# Schematic_Transmitter.net
KiCad netlist of a schematic drawn in EasyEDA
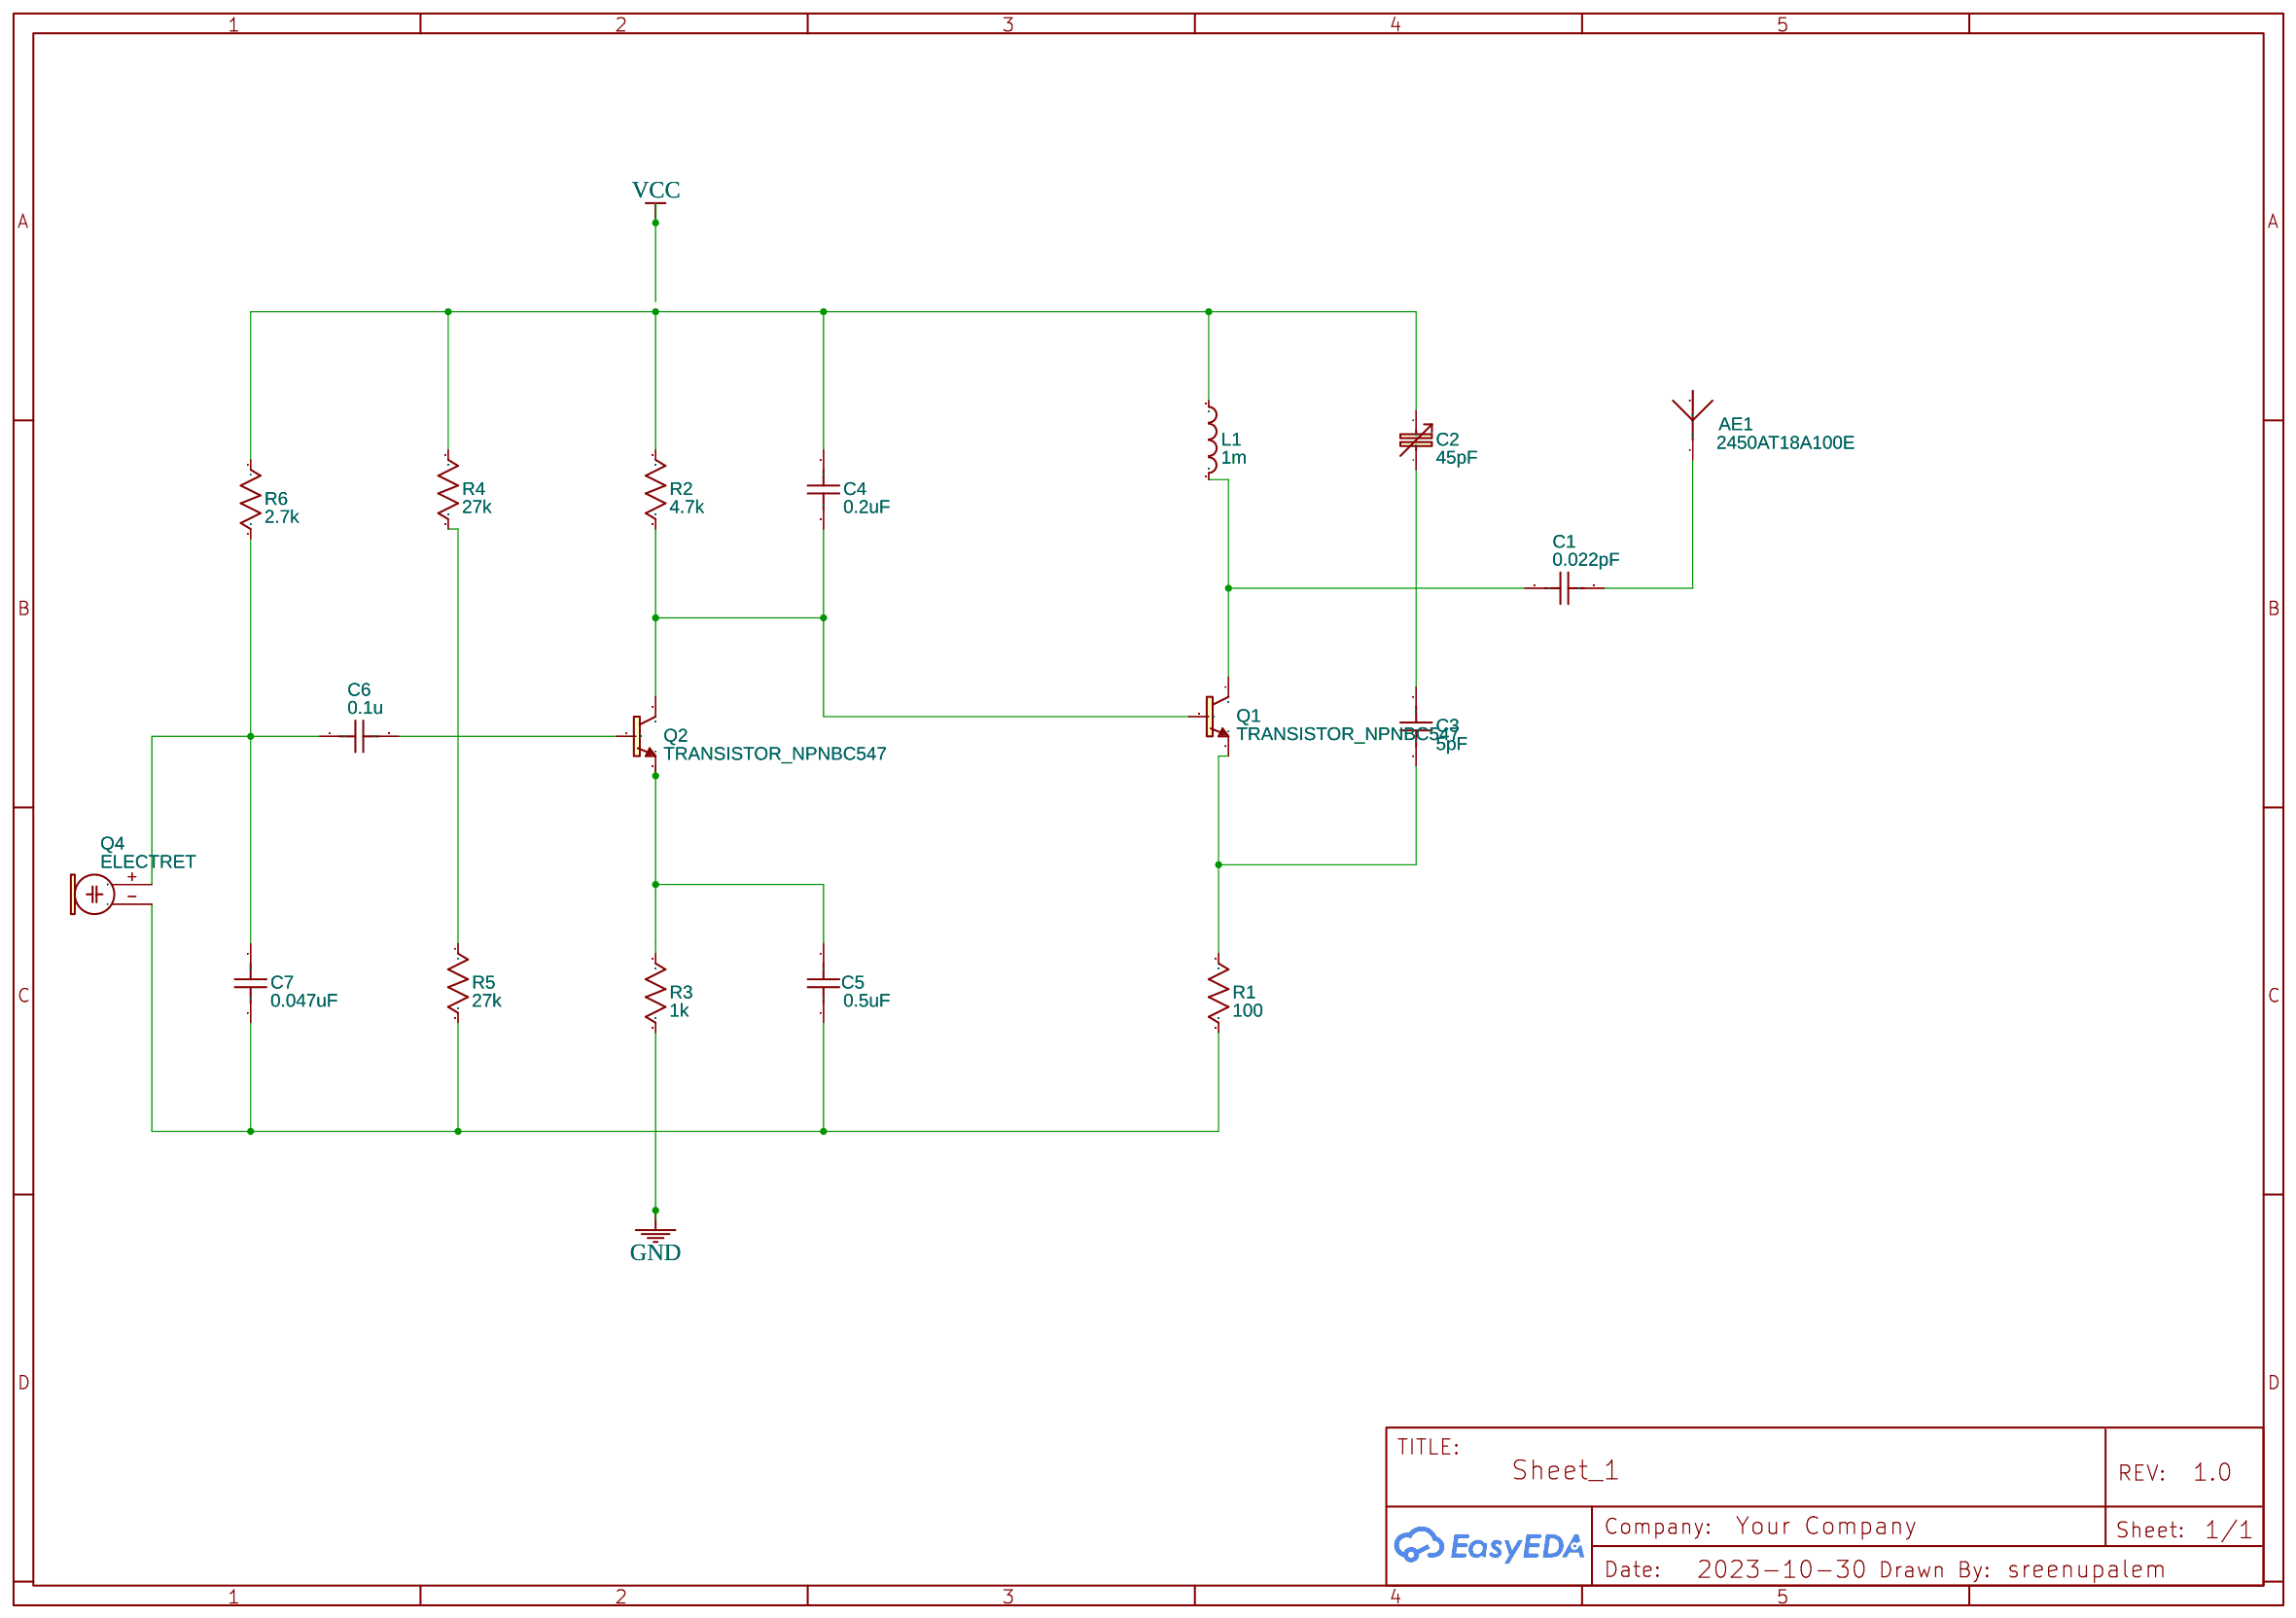
[diagram p0: schematic sheet]

(export (version "E")
  (design (tool "Eeschema 10.0.6"))
  (components
    (comp (ref "AE1")
      (value "2450AT18A100E")
      (fields (field (name "Manufacturer") "JOHANSON(约翰逊)"))
      (libsource (lib "") (part "2450AT18A100E"))
    )
    (comp (ref "C1") (value "0.022pF") (libsource (lib "") (part "C_0603_US_1")))
    (comp (ref "C2") (value "45pF") (libsource (lib "") (part "CAP_ADJSMD")))
    (comp (ref "C3") (value "5pF") (libsource (lib "") (part "C_0603_US")))
    (comp (ref "C4") (value "0.2uF") (libsource (lib "") (part "C_0603_US")))
    (comp (ref "C5") (value "0.5uF") (libsource (lib "") (part "C_0603_US")))
    (comp (ref "C6") (value "0.1u") (libsource (lib "") (part "C_0603_US_1")))
    (comp (ref "C7") (value "0.047uF") (libsource (lib "") (part "C_0603_US")))
    (comp (ref "L1") (value "1m") (libsource (lib "") (part "L0603_US")))
    (comp (ref "Q1") (value "TRANSISTOR_NPNBC547") (libsource (lib "") (part "TRANSISTOR_NPNBC547")))
    (comp (ref "Q2") (value "TRANSISTOR_NPNBC547") (libsource (lib "") (part "TRANSISTOR_NPNBC547")))
    (comp (ref "Q4") (value "ELECTRET") (libsource (lib "") (part "ELECTRET")))
    (comp (ref "R1") (value "100") (libsource (lib "") (part "R_0603_US")))
    (comp (ref "R2") (value "4.7k") (libsource (lib "") (part "R_0603_US")))
    (comp (ref "R3") (value "1k") (libsource (lib "") (part "R_0603_US")))
    (comp (ref "R4") (value "27k") (libsource (lib "") (part "R_0603_US")))
    (comp (ref "R5") (value "27k") (libsource (lib "") (part "R_0603_US")))
    (comp (ref "R6") (value "2.7k") (libsource (lib "") (part "R_0603_US")))
  )
  (nets
    (net (code "1") (name "GND") (class "Default")
      (node (ref "R3") (pin "2") (pinfunction "2_2") (pintype "unspecified"))
    )
    (net (code "2") (name "Net-(AE1-ANT)") (class "Default")
      (node (ref "AE1") (pin "1") (pinfunction "ANT_1") (pintype "unspecified"))
      (node (ref "C1") (pin "2") (pinfunction "2_2") (pintype "unspecified"))
    )
    (net (code "3") (name "Net-(C2-3)") (class "Default")
      (node (ref "C2") (pin "+") (pinfunction "3_+") (pintype "unspecified"))
      (node (ref "C4") (pin "1") (pinfunction "1_1") (pintype "unspecified"))
      (node (ref "L1") (pin "1") (pinfunction "1_1") (pintype "unspecified"))
      (node (ref "R2") (pin "1") (pinfunction "1_1") (pintype "unspecified"))
      (node (ref "R4") (pin "1") (pinfunction "1_1") (pintype "unspecified"))
      (node (ref "R6") (pin "1") (pinfunction "1_1") (pintype "unspecified"))
    )
    (net (code "4") (name "Net-(C2-4)") (class "Default")
      (node (ref "C2") (pin "-") (pinfunction "4_-") (pintype "unspecified"))
      (node (ref "C3") (pin "1") (pinfunction "1_1") (pintype "unspecified"))
    )
    (net (code "5") (name "Net-(Q1-B)") (class "Default")
      (node (ref "C4") (pin "2") (pinfunction "2_2") (pintype "unspecified"))
      (node (ref "Q1") (pin "2") (pinfunction "B_2") (pintype "unspecified"))
      (node (ref "Q2") (pin "1") (pinfunction "C_1") (pintype "unspecified"))
      (node (ref "R2") (pin "2") (pinfunction "2_2") (pintype "unspecified"))
    )
    (net (code "6") (name "Net-(Q1-C)") (class "Default")
      (node (ref "C1") (pin "1") (pinfunction "1_1") (pintype "unspecified"))
      (node (ref "L1") (pin "2") (pinfunction "2_2") (pintype "unspecified"))
      (node (ref "Q1") (pin "1") (pinfunction "C_1") (pintype "unspecified"))
    )
    (net (code "7") (name "Net-(Q1-E)") (class "Default")
      (node (ref "C3") (pin "2") (pinfunction "2_2") (pintype "unspecified"))
      (node (ref "Q1") (pin "3") (pinfunction "E_3") (pintype "unspecified"))
      (node (ref "R1") (pin "1") (pinfunction "1_1") (pintype "unspecified"))
    )
    (net (code "8") (name "Net-(Q2-B)") (class "Default")
      (node (ref "C6") (pin "2") (pinfunction "2_2") (pintype "unspecified"))
      (node (ref "Q2") (pin "2") (pinfunction "B_2") (pintype "unspecified"))
    )
    (net (code "9") (name "Net-(Q2-E)") (class "Default")
      (node (ref "C5") (pin "1") (pinfunction "1_1") (pintype "unspecified"))
      (node (ref "Q2") (pin "3") (pinfunction "E_3") (pintype "unspecified"))
      (node (ref "R3") (pin "1") (pinfunction "1_1") (pintype "unspecified"))
    )
    (net (code "10") (name "Net-(Q4-1)") (class "Default")
      (node (ref "C5") (pin "2") (pinfunction "2_2") (pintype "unspecified"))
      (node (ref "C7") (pin "2") (pinfunction "2_2") (pintype "unspecified"))
      (node (ref "Q4") (pin "-") (pinfunction "1_-") (pintype "unspecified"))
      (node (ref "R1") (pin "2") (pinfunction "2_2") (pintype "unspecified"))
      (node (ref "R5") (pin "2") (pinfunction "2_2") (pintype "unspecified"))
    )
    (net (code "11") (name "Net-(Q4-2)") (class "Default")
      (node (ref "C6") (pin "1") (pinfunction "1_1") (pintype "unspecified"))
      (node (ref "C7") (pin "1") (pinfunction "1_1") (pintype "unspecified"))
      (node (ref "Q4") (pin "+") (pinfunction "2_+") (pintype "unspecified"))
      (node (ref "R6") (pin "2") (pinfunction "2_2") (pintype "unspecified"))
    )
    (net (code "12") (name "Net-(R4-Pad2)") (class "Default")
      (node (ref "R4") (pin "2") (pinfunction "2_2") (pintype "unspecified"))
      (node (ref "R5") (pin "1") (pinfunction "1_1") (pintype "unspecified"))
    )
    (net (code "14") (name "unconnected-(AE1-Pad2)") (class "Default")
      (node (ref "AE1") (pin "2") (pinfunction "2_2") (pintype "unspecified"))
    )
  )
)
